# MRF24J40MA_Breakout.net
KiCad netlist of a schematic drawn in EAGLE
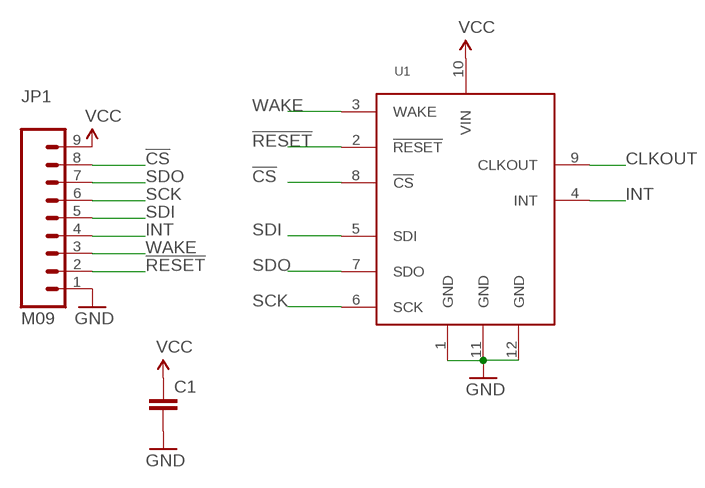
[diagram p0: schematic, sheet 1]

(export (version "E")
  (design (tool "Eeschema 10.0.6"))
  (components
    (comp (ref "C1")
      (value "CAP0603-CAP")
      (footprint "eagle-import:0603-CAP")
      (libsource (lib "eagle-import") (part "CAP0603-CAP"))
    )
    (comp (ref "JP1")
      (value "M09")
      (footprint "eagle-import:1X09")
      (libsource (lib "eagle-import") (part "M09"))
    )
    (comp (ref "U1")
      (value "MRF24J40MA\"")
      (footprint "eagle-import:MRF24J40MA")
      (libsource (lib "eagle-import") (part "MRF24J40MA{dblquote}"))
    )
  )
  (nets
    (net (code "1") (name "/CLKOUT") (class "Default")
      (node (ref "U1") (pin "9") (pinfunction "CLKOUT_9") (pintype "bidirectional"))
    )
    (net (code "2") (name "/INT") (class "Default")
      (node (ref "JP1") (pin "4") (pinfunction "4_4") (pintype "passive"))
      (node (ref "U1") (pin "4") (pinfunction "INT_4") (pintype "bidirectional"))
    )
    (net (code "3") (name "/SCK") (class "Default")
      (node (ref "JP1") (pin "6") (pinfunction "6_6") (pintype "passive"))
      (node (ref "U1") (pin "6") (pinfunction "SCK_6") (pintype "bidirectional"))
    )
    (net (code "4") (name "/SDI") (class "Default")
      (node (ref "JP1") (pin "5") (pinfunction "5_5") (pintype "passive"))
      (node (ref "U1") (pin "5") (pinfunction "SDI_5") (pintype "bidirectional"))
    )
    (net (code "5") (name "/SDO") (class "Default")
      (node (ref "JP1") (pin "7") (pinfunction "7_7") (pintype "passive"))
      (node (ref "U1") (pin "7") (pinfunction "SDO_7") (pintype "bidirectional"))
    )
    (net (code "6") (name "/WAKE") (class "Default")
      (node (ref "JP1") (pin "3") (pinfunction "3_3") (pintype "passive"))
      (node (ref "U1") (pin "3") (pinfunction "WAKE_3") (pintype "bidirectional"))
    )
    (net (code "7") (name "/~{CS}") (class "Default")
      (node (ref "JP1") (pin "8") (pinfunction "8_8") (pintype "passive"))
      (node (ref "U1") (pin "8") (pinfunction "~{CS}_8") (pintype "bidirectional"))
    )
    (net (code "8") (name "/~{RESET}") (class "Default")
      (node (ref "JP1") (pin "2") (pinfunction "2_2") (pintype "passive"))
      (node (ref "U1") (pin "2") (pinfunction "~{RESET}_2") (pintype "bidirectional"))
    )
    (net (code "9") (name "GND") (class "Default")
      (node (ref "C1") (pin "2") (pinfunction "2_2") (pintype "passive"))
      (node (ref "JP1") (pin "1") (pinfunction "1_1") (pintype "passive"))
      (node (ref "U1") (pin "1") (pinfunction "GND_1") (pintype "power_in"))
      (node (ref "U1") (pin "11") (pinfunction "GND_11") (pintype "power_in"))
      (node (ref "U1") (pin "12") (pinfunction "GND_12") (pintype "power_in"))
    )
    (net (code "10") (name "VCC") (class "Default")
      (node (ref "C1") (pin "1") (pinfunction "1_1") (pintype "passive"))
      (node (ref "JP1") (pin "9") (pinfunction "9_9") (pintype "passive"))
      (node (ref "U1") (pin "10") (pinfunction "VIN_10") (pintype "bidirectional"))
    )
  )
)
